# Shift_Reg.net
KiCad netlist of a schematic drawn in Altium Designer
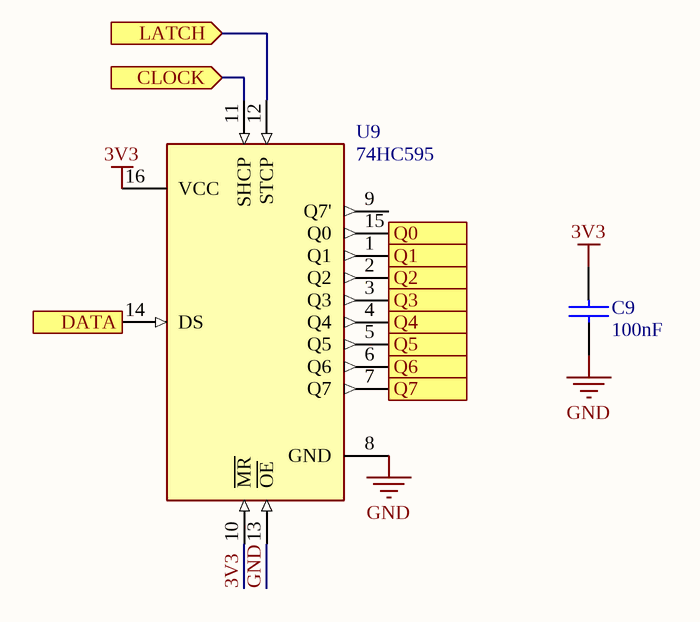
[diagram p0: Shift Reg.SchDoc]

(export (version "E")
  (design (tool "Eeschema 10.0.6"))
  (components
    (comp (ref "C9") (value "100nF") (footprint "0805") (libsource (lib "LIBPIOIX") (part "CAP")))
    (comp (ref "U9")
      (value "74HC595")
      (footprint "SOIC16N")
      (libsource (lib "Esquematicos") (part "74HC595"))
    )
  )
  (nets
    (net (code "1") (name "/CLOCK") (class "Default")
      (node (ref "U9") (pin "11") (pinfunction "SHCP_11") (pintype "input"))
    )
    (net (code "2") (name "/DATA") (class "Default")
      (node (ref "U9") (pin "14") (pinfunction "DS_14") (pintype "input"))
    )
    (net (code "3") (name "/LATCH") (class "Default")
      (node (ref "U9") (pin "12") (pinfunction "STCP_12") (pintype "input"))
    )
    (net (code "4") (name "/Q0") (class "Default")
      (node (ref "U9") (pin "15") (pinfunction "Q0_15") (pintype "output"))
    )
    (net (code "5") (name "/Q1") (class "Default")
      (node (ref "U9") (pin "1") (pinfunction "Q1_1") (pintype "output"))
    )
    (net (code "6") (name "/Q2") (class "Default")
      (node (ref "U9") (pin "2") (pinfunction "Q2_2") (pintype "output"))
    )
    (net (code "7") (name "/Q3") (class "Default")
      (node (ref "U9") (pin "3") (pinfunction "Q3_3") (pintype "output"))
    )
    (net (code "8") (name "/Q4") (class "Default")
      (node (ref "U9") (pin "4") (pinfunction "Q4_4") (pintype "output"))
    )
    (net (code "9") (name "/Q5") (class "Default")
      (node (ref "U9") (pin "5") (pinfunction "Q5_5") (pintype "output"))
    )
    (net (code "10") (name "/Q6") (class "Default")
      (node (ref "U9") (pin "6") (pinfunction "Q6_6") (pintype "output"))
    )
    (net (code "11") (name "/Q7") (class "Default")
      (node (ref "U9") (pin "7") (pinfunction "Q7_7") (pintype "output"))
    )
    (net (code "12") (name "3V3") (class "Default")
      (node (ref "C9") (pin "1") (pinfunction "1_1") (pintype "passive"))
      (node (ref "U9") (pin "10") (pinfunction "~{MR}_10") (pintype "input"))
      (node (ref "U9") (pin "16") (pinfunction "VCC_16") (pintype "power_in"))
    )
    (net (code "13") (name "GND") (class "Default")
      (node (ref "C9") (pin "2") (pinfunction "2_2") (pintype "passive"))
      (node (ref "U9") (pin "13") (pinfunction "~{OE}_13") (pintype "input"))
      (node (ref "U9") (pin "8") (pinfunction "GND_8") (pintype "power_in"))
    )
    (net (code "14") (name "unconnected-(U9-Q7'-Pad9)") (class "Default")
      (node (ref "U9") (pin "9") (pinfunction "Q7'_9") (pintype "output"))
    )
  )
)
